# WifiAndPower.net
KiCad netlist of a schematic drawn in Altium Designer
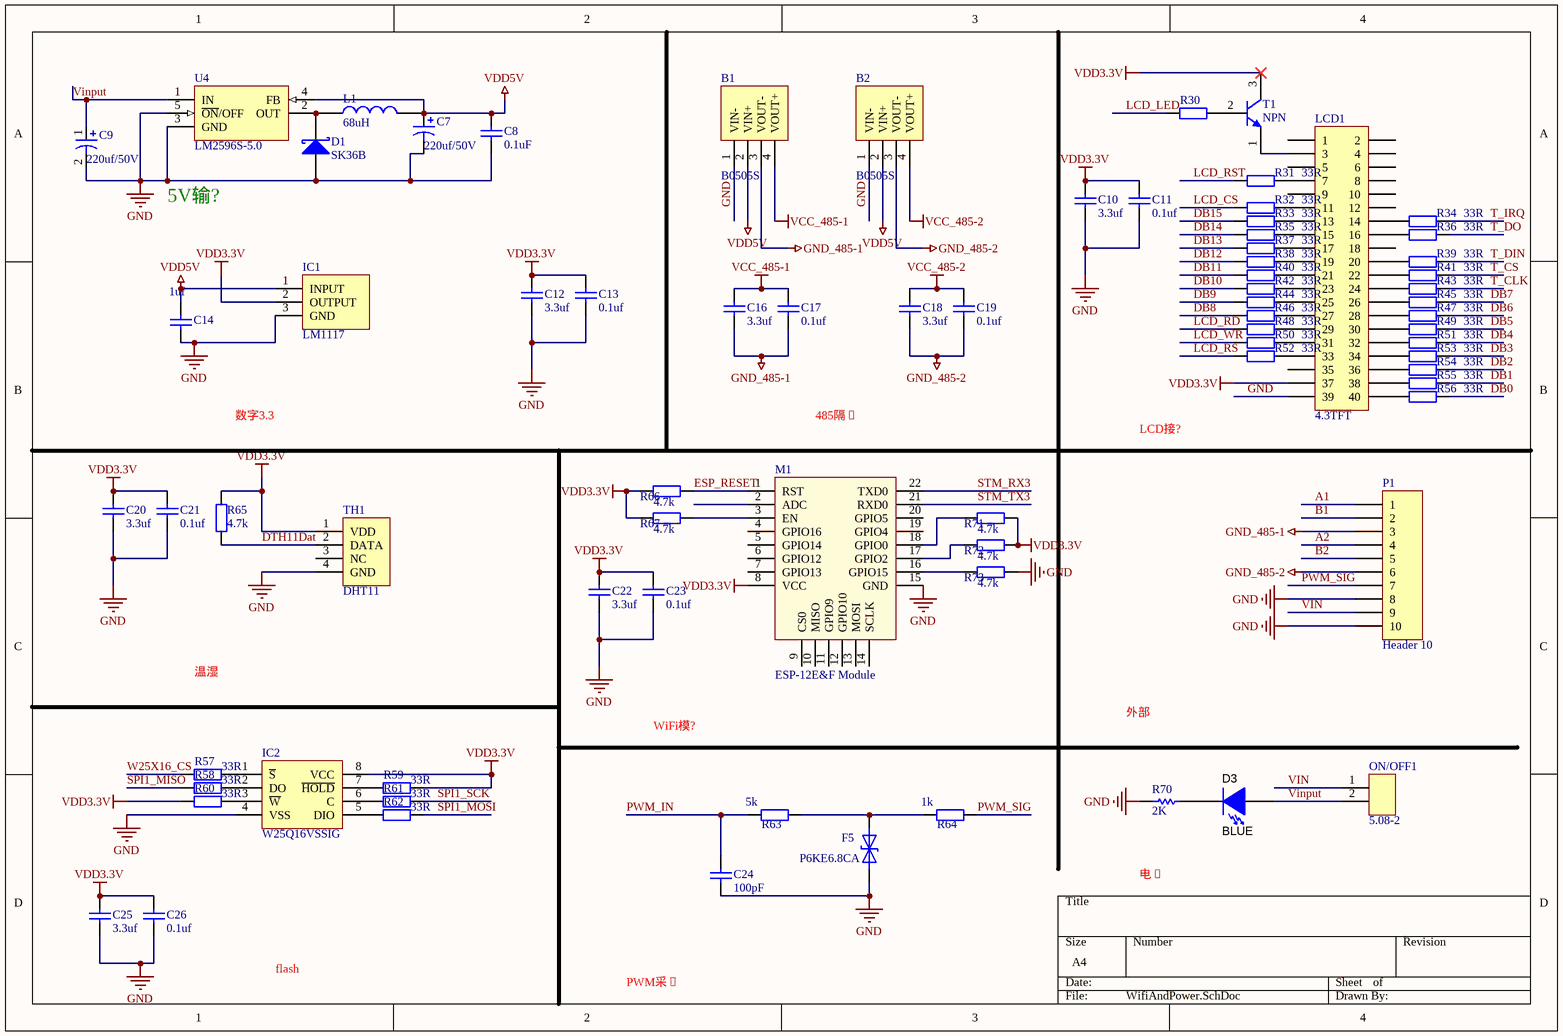
[diagram p0: WifiAndPower.SchDoc]

(export (version "E")
  (design (tool "Eeschema 10.0.6"))
  (components
    (comp (ref "B1") (value "B0505S") (footprint "B0505S") (libsource (lib "S1") (part "B0505S")))
    (comp (ref "B2") (value "B0505S") (footprint "B0505S") (libsource (lib "S1") (part "B0505S")))
    (comp (ref "C7")
      (value "220uf/50V")
      (footprint "PLAS8*10")
      (description "Polarized Capacitor (Radial)")
      (fields (field (name "Comment") "Cap Pol1") (field (name "PUBLISHER") "Altium Limited"))
      (libsource (lib "Miscellaneous Devices") (part "Cap Pol1"))
    )
    (comp (ref "C8")
      (value "0.1uF")
      (footprint "C0805")
      (description "Capacitor")
      (fields (field (name "Comment") "Cap") (field (name "PUBLISHER") "Altium Limited"))
      (libsource (lib "main board") (part "Cap_2"))
    )
    (comp (ref "C9")
      (value "220uf/50V")
      (footprint "PLAS8*10")
      (description "Polarized Capacitor (Radial)")
      (fields (field (name "Comment") "Cap Pol1") (field (name "PUBLISHER") "Altium Limited"))
      (libsource (lib "") (part "Cap Pol1_1"))
    )
    (comp (ref "C10")
      (value "3.3uf")
      (footprint "C0805")
      (description "Capacitor")
      (fields
        (field (name "MANUFACTURER") "Generic Components")
        (field (name "Comment") "Cap")
        (field (name "PUBLISHER") "Altium Hobart Technology Centre")
      )
      (libsource (lib "Miscellaneous Devices") (part "Cap"))
    )
    (comp (ref "C11")
      (value "0.1uf")
      (footprint "C0805")
      (description "Capacitor")
      (fields
        (field (name "MANUFACTURER") "Generic Components")
        (field (name "Comment") "Cap")
        (field (name "PUBLISHER") "Altium Hobart Technology Centre")
      )
      (libsource (lib "Miscellaneous Devices") (part "Cap"))
    )
    (comp (ref "C12")
      (value "3.3uf")
      (footprint "C0805")
      (description "Capacitor")
      (fields
        (field (name "MANUFACTURER") "Generic Components")
        (field (name "Comment") "Cap")
        (field (name "PUBLISHER") "Altium Hobart Technology Centre")
      )
      (libsource (lib "Miscellaneous Devices") (part "Cap"))
    )
    (comp (ref "C13")
      (value "0.1uf")
      (footprint "C0805")
      (description "Capacitor")
      (fields
        (field (name "MANUFACTURER") "Generic Components")
        (field (name "Comment") "Cap")
        (field (name "PUBLISHER") "Altium Hobart Technology Centre")
      )
      (libsource (lib "Miscellaneous Devices") (part "Cap"))
    )
    (comp (ref "C14")
      (value "1uf")
      (footprint "C0805")
      (description "Capacitor")
      (fields
        (field (name "MANUFACTURER") "Generic Components")
        (field (name "Comment") "Cap")
        (field (name "PUBLISHER") "Altium Hobart Technology Centre")
      )
      (libsource (lib "Miscellaneous Devices") (part "Cap"))
    )
    (comp (ref "C16")
      (value "3.3uf")
      (footprint "C0805")
      (description "Capacitor")
      (fields
        (field (name "MANUFACTURER") "Generic Components")
        (field (name "Comment") "Cap")
        (field (name "PUBLISHER") "Altium Hobart Technology Centre")
      )
      (libsource (lib "Miscellaneous Devices") (part "Cap"))
    )
    (comp (ref "C17")
      (value "0.1uf")
      (footprint "C0805")
      (description "Capacitor")
      (fields
        (field (name "MANUFACTURER") "Generic Components")
        (field (name "Comment") "Cap")
        (field (name "PUBLISHER") "Altium Hobart Technology Centre")
      )
      (libsource (lib "Miscellaneous Devices") (part "Cap"))
    )
    (comp (ref "C18")
      (value "3.3uf")
      (footprint "C0805")
      (description "Capacitor")
      (fields
        (field (name "MANUFACTURER") "Generic Components")
        (field (name "Comment") "Cap")
        (field (name "PUBLISHER") "Altium Hobart Technology Centre")
      )
      (libsource (lib "Miscellaneous Devices") (part "Cap"))
    )
    (comp (ref "C19")
      (value "0.1uf")
      (footprint "C0805")
      (description "Capacitor")
      (fields
        (field (name "MANUFACTURER") "Generic Components")
        (field (name "Comment") "Cap")
        (field (name "PUBLISHER") "Altium Hobart Technology Centre")
      )
      (libsource (lib "Miscellaneous Devices") (part "Cap"))
    )
    (comp (ref "C20")
      (value "3.3uf")
      (footprint "C0805")
      (description "Capacitor")
      (fields
        (field (name "MANUFACTURER") "Generic Components")
        (field (name "Comment") "Cap")
        (field (name "PUBLISHER") "Altium Hobart Technology Centre")
      )
      (libsource (lib "Miscellaneous Devices") (part "Cap"))
    )
    (comp (ref "C21")
      (value "0.1uf")
      (footprint "C0805")
      (description "Capacitor")
      (fields
        (field (name "MANUFACTURER") "Generic Components")
        (field (name "Comment") "Cap")
        (field (name "PUBLISHER") "Altium Hobart Technology Centre")
      )
      (libsource (lib "Miscellaneous Devices") (part "Cap"))
    )
    (comp (ref "C22")
      (value "3.3uf")
      (footprint "C0805")
      (description "Capacitor")
      (fields
        (field (name "MANUFACTURER") "Generic Components")
        (field (name "Comment") "Cap")
        (field (name "PUBLISHER") "Altium Hobart Technology Centre")
      )
      (libsource (lib "Miscellaneous Devices") (part "Cap"))
    )
    (comp (ref "C23")
      (value "0.1uf")
      (footprint "C0805")
      (description "Capacitor")
      (fields
        (field (name "MANUFACTURER") "Generic Components")
        (field (name "Comment") "Cap")
        (field (name "PUBLISHER") "Altium Hobart Technology Centre")
      )
      (libsource (lib "Miscellaneous Devices") (part "Cap"))
    )
    (comp (ref "C24")
      (value "100pF")
      (footprint "C0805")
      (description "Capacitor")
      (fields
        (field (name "MANUFACTURER") "Generic Components")
        (field (name "Comment") "Cap")
        (field (name "PUBLISHER") "Altium Hobart Technology Centre")
      )
      (libsource (lib "Miscellaneous Devices") (part "Cap"))
    )
    (comp (ref "C25")
      (value "3.3uf")
      (footprint "C0805")
      (description "Capacitor")
      (fields
        (field (name "MANUFACTURER") "Generic Components")
        (field (name "Comment") "Cap")
        (field (name "PUBLISHER") "Altium Hobart Technology Centre")
      )
      (libsource (lib "Miscellaneous Devices") (part "Cap"))
    )
    (comp (ref "C26")
      (value "0.1uf")
      (footprint "C0805")
      (description "Capacitor")
      (fields
        (field (name "MANUFACTURER") "Generic Components")
        (field (name "Comment") "Cap")
        (field (name "PUBLISHER") "Altium Hobart Technology Centre")
      )
      (libsource (lib "Miscellaneous Devices") (part "Cap"))
    )
    (comp (ref "D1")
      (value "SK36B")
      (footprint "SMB")
      (description "Schottky Diode")
      (fields (field (name "PUBLISHER") "Altium Limited"))
      (libsource (lib "Miscellaneous Devices") (part "D Schottky"))
    )
    (comp (ref "D3")
      (value "BLUE")
      (footprint "D0805")
      (description "LED, GREEN SMD")
      (fields
        (field (name "MANUFACTURER") "Rohm")
        (field (name "PARTNUMBER") "SML-P12YTT86")
        (field (name "PUBLISHER") "Texas Instruments")
      )
      (libsource (lib "REl") (part "SML-P12YTT86"))
    )
    (comp (ref "F5") (value "P6KE6.8CA") (description "快速瞬变二极管") (libsource (lib "*") (part "TVS")))
    (comp (ref "IC1") (value "LM1117") (footprint "LM1117") (libsource (lib "S1") (part "LM1117")))
    (comp (ref "IC2") (value "W25Q16VSSIG") (footprint "wsop8") (libsource (lib "S1") (part "A25L080")))
    (comp (ref "L1") (value "68uH") (footprint "PCBH101") (libsource (lib "µçÔ´°å") (part "INDUCTOR")))
    (comp (ref "LCD1") (value "4.3TFT") (footprint "2.4TFT") (libsource (lib "S1") (part "4.3TFT")))
    (comp (ref "M1")
      (value "ESP-12E&F Module")
      (footprint "ESP-12E&F Module")
      (libsource (lib "ESP-12E&F Module") (part "ESP-12E&F Module"))
    )
    (comp (ref "ON/OFF1") (value "5.08-2") (footprint "SensorA") (libsource (lib "S1") (part "5.08-2")))
    (comp (ref "P1")
      (value "Header 10")
      (footprint "3.5-10")
      (description "Header, 10-Pin")
      (fields (field (name "PUBLISHER") "Altium Limited"))
      (libsource (lib "Miscellaneous Connectors") (part "Header 10"))
    )
    (comp (ref "R30") (value "Res2") (footprint "0805") (libsource (lib "") (part "RES_2")))
    (comp (ref "R31")
      (value "33R")
      (footprint "0805")
      (fields (field (name "Comment") "Res2"))
      (libsource (lib "") (part "RES_2"))
    )
    (comp (ref "R32")
      (value "33R")
      (footprint "0805")
      (fields (field (name "Comment") "Res2"))
      (libsource (lib "") (part "RES_2"))
    )
    (comp (ref "R33")
      (value "33R")
      (footprint "0805")
      (fields (field (name "Comment") "Res2"))
      (libsource (lib "") (part "RES_2"))
    )
    (comp (ref "R34")
      (value "33R")
      (footprint "0805")
      (fields (field (name "Comment") "Res2"))
      (libsource (lib "") (part "RES_2"))
    )
    (comp (ref "R35")
      (value "33R")
      (footprint "0805")
      (fields (field (name "Comment") "Res2"))
      (libsource (lib "") (part "RES_2"))
    )
    (comp (ref "R36")
      (value "33R")
      (footprint "0805")
      (fields (field (name "Comment") "Res2"))
      (libsource (lib "") (part "RES_2"))
    )
    (comp (ref "R37")
      (value "33R")
      (footprint "0805")
      (fields (field (name "Comment") "Res2"))
      (libsource (lib "") (part "RES_2"))
    )
    (comp (ref "R38")
      (value "33R")
      (footprint "0805")
      (fields (field (name "Comment") "Res2"))
      (libsource (lib "") (part "RES_2"))
    )
    (comp (ref "R39")
      (value "33R")
      (footprint "0805")
      (fields (field (name "Comment") "Res2"))
      (libsource (lib "") (part "RES_2"))
    )
    (comp (ref "R40")
      (value "33R")
      (footprint "0805")
      (fields (field (name "Comment") "Res2"))
      (libsource (lib "") (part "RES_2"))
    )
    (comp (ref "R41")
      (value "33R")
      (footprint "0805")
      (fields (field (name "Comment") "Res2"))
      (libsource (lib "") (part "RES_2"))
    )
    (comp (ref "R42")
      (value "33R")
      (footprint "0805")
      (fields (field (name "Comment") "Res2"))
      (libsource (lib "") (part "RES_2"))
    )
    (comp (ref "R43")
      (value "33R")
      (footprint "0805")
      (fields (field (name "Comment") "Res2"))
      (libsource (lib "") (part "RES_2"))
    )
    (comp (ref "R44")
      (value "33R")
      (footprint "0805")
      (fields (field (name "Comment") "Res2"))
      (libsource (lib "") (part "RES_2"))
    )
    (comp (ref "R45")
      (value "33R")
      (footprint "0805")
      (fields (field (name "Comment") "Res2"))
      (libsource (lib "") (part "RES_2"))
    )
    (comp (ref "R46")
      (value "33R")
      (footprint "0805")
      (fields (field (name "Comment") "Res2"))
      (libsource (lib "") (part "RES_2"))
    )
    (comp (ref "R47")
      (value "33R")
      (footprint "0805")
      (fields (field (name "Comment") "Res2"))
      (libsource (lib "") (part "RES_2"))
    )
    (comp (ref "R48")
      (value "33R")
      (footprint "0805")
      (fields (field (name "Comment") "Res2"))
      (libsource (lib "") (part "RES_2"))
    )
    (comp (ref "R49")
      (value "33R")
      (footprint "0805")
      (fields (field (name "Comment") "Res2"))
      (libsource (lib "") (part "RES_2"))
    )
    (comp (ref "R50")
      (value "33R")
      (footprint "0805")
      (fields (field (name "Comment") "Res2"))
      (libsource (lib "") (part "RES_2"))
    )
    (comp (ref "R51")
      (value "33R")
      (footprint "0805")
      (fields (field (name "Comment") "Res2"))
      (libsource (lib "") (part "RES_2"))
    )
    (comp (ref "R52")
      (value "33R")
      (footprint "0805")
      (fields (field (name "Comment") "Res2"))
      (libsource (lib "") (part "RES_2"))
    )
    (comp (ref "R53")
      (value "33R")
      (footprint "0805")
      (fields (field (name "Comment") "Res2"))
      (libsource (lib "") (part "RES_2"))
    )
    (comp (ref "R54")
      (value "33R")
      (footprint "0805")
      (fields (field (name "Comment") "Res2"))
      (libsource (lib "") (part "RES_2"))
    )
    (comp (ref "R55")
      (value "33R")
      (footprint "0805")
      (fields (field (name "Comment") "Res2"))
      (libsource (lib "") (part "RES_2"))
    )
    (comp (ref "R56")
      (value "33R")
      (footprint "0805")
      (fields (field (name "Comment") "Res2"))
      (libsource (lib "") (part "RES_2"))
    )
    (comp (ref "R57")
      (value "33R")
      (footprint "0805")
      (fields (field (name "Comment") "Res2"))
      (libsource (lib "") (part "RES_2"))
    )
    (comp (ref "R58")
      (value "33R")
      (footprint "0805")
      (fields (field (name "Comment") "Res2"))
      (libsource (lib "") (part "RES_2"))
    )
    (comp (ref "R59")
      (value "33R")
      (footprint "0805")
      (fields (field (name "Comment") "Res2"))
      (libsource (lib "") (part "RES_2"))
    )
    (comp (ref "R60")
      (value "33R")
      (footprint "0805")
      (fields (field (name "Comment") "Res2"))
      (libsource (lib "") (part "RES_2"))
    )
    (comp (ref "R61")
      (value "33R")
      (footprint "0805")
      (fields (field (name "Comment") "Res2"))
      (libsource (lib "") (part "RES_2"))
    )
    (comp (ref "R62")
      (value "33R")
      (footprint "0805")
      (fields (field (name "Comment") "Res2"))
      (libsource (lib "") (part "RES_2"))
    )
    (comp (ref "R63")
      (value "5k")
      (footprint "0805")
      (fields (field (name "Comment") "RES"))
      (libsource (lib "S1") (part "RES"))
    )
    (comp (ref "R64")
      (value "1k")
      (footprint "0805")
      (fields (field (name "Comment") "RES"))
      (libsource (lib "S1") (part "RES"))
    )
    (comp (ref "R65")
      (value "4.7k")
      (footprint "0805")
      (fields (field (name "Comment") "Res2"))
      (libsource (lib "") (part "RES_1"))
    )
    (comp (ref "R66")
      (value "4.7k")
      (footprint "0805")
      (fields (field (name "Comment") "Res2"))
      (libsource (lib "S1") (part "RES"))
    )
    (comp (ref "R67")
      (value "4.7k")
      (footprint "0805")
      (fields (field (name "Comment") "Res2"))
      (libsource (lib "S1") (part "RES"))
    )
    (comp (ref "R70")
      (value "2K")
      (footprint "0805")
      (description "Semiconductor Resistor")
      (fields (field (name "Comment") "Res Semi") (field (name "PUBLISHER") "Altium Limited"))
      (libsource (lib "Miscellaneous Devices") (part "Res Semi"))
    )
    (comp (ref "R71")
      (value "4.7k")
      (footprint "0805")
      (fields (field (name "Comment") "Res2"))
      (libsource (lib "S1") (part "RES"))
    )
    (comp (ref "R72")
      (value "4.7k")
      (footprint "0805")
      (fields (field (name "Comment") "Res2"))
      (libsource (lib "S1") (part "RES"))
    )
    (comp (ref "R73")
      (value "4.7k")
      (footprint "0805")
      (fields (field (name "Comment") "Res2"))
      (libsource (lib "S1") (part "RES"))
    )
    (comp (ref "T1") (value "NPN") (footprint "2N3904") (libsource (lib "S1") (part "NPN")))
    (comp (ref "TH1") (value "DHT11") (footprint "DHT11") (libsource (lib "S1") (part "DHT11")))
    (comp (ref "U4")
      (value "LM2596S-5.0")
      (footprint "TS5B_M")
      (description "Simple Switcher Power Converter 150 kHz 3A Step Down Voltage Regulator")
      (fields (field (name "PUBLISHER") "Altium Limited"))
      (libsource (lib "NSC Power Mgt Switching Regulator") (part "LM2596S-5.0"))
    )
  )
  (nets
    (net (code "1") (name "/A1") (class "Default")
      (node (ref "P1") (pin "1") (pinfunction "1_1") (pintype "passive"))
    )
    (net (code "2") (name "/A2") (class "Default")
      (node (ref "P1") (pin "4") (pinfunction "4_4") (pintype "passive"))
    )
    (net (code "3") (name "/B1") (class "Default")
      (node (ref "P1") (pin "2") (pinfunction "2_2") (pintype "passive"))
    )
    (net (code "4") (name "/B2") (class "Default")
      (node (ref "P1") (pin "5") (pinfunction "5_5") (pintype "passive"))
    )
    (net (code "5") (name "/DB0") (class "Default")
      (node (ref "R56") (pin "2") (pinfunction "2_2") (pintype "passive"))
    )
    (net (code "6") (name "/DB1") (class "Default")
      (node (ref "R55") (pin "2") (pinfunction "2_2") (pintype "passive"))
    )
    (net (code "7") (name "/DB2") (class "Default")
      (node (ref "R54") (pin "2") (pinfunction "2_2") (pintype "passive"))
    )
    (net (code "8") (name "/DB3") (class "Default")
      (node (ref "R53") (pin "2") (pinfunction "2_2") (pintype "passive"))
    )
    (net (code "9") (name "/DB4") (class "Default")
      (node (ref "R51") (pin "2") (pinfunction "2_2") (pintype "passive"))
    )
    (net (code "10") (name "/DB5") (class "Default")
      (node (ref "R49") (pin "2") (pinfunction "2_2") (pintype "passive"))
    )
    (net (code "11") (name "/DB6") (class "Default")
      (node (ref "R47") (pin "2") (pinfunction "2_2") (pintype "passive"))
    )
    (net (code "12") (name "/DB7") (class "Default")
      (node (ref "R45") (pin "2") (pinfunction "2_2") (pintype "passive"))
    )
    (net (code "13") (name "/DB8") (class "Default")
      (node (ref "R46") (pin "1") (pinfunction "1_1") (pintype "passive"))
    )
    (net (code "14") (name "/DB9") (class "Default")
      (node (ref "R44") (pin "1") (pinfunction "1_1") (pintype "passive"))
    )
    (net (code "15") (name "/DB10") (class "Default")
      (node (ref "R42") (pin "1") (pinfunction "1_1") (pintype "passive"))
    )
    (net (code "16") (name "/DB11") (class "Default")
      (node (ref "R40") (pin "1") (pinfunction "1_1") (pintype "passive"))
    )
    (net (code "17") (name "/DB12") (class "Default")
      (node (ref "R38") (pin "1") (pinfunction "1_1") (pintype "passive"))
    )
    (net (code "18") (name "/DB13") (class "Default")
      (node (ref "R37") (pin "1") (pinfunction "1_1") (pintype "passive"))
    )
    (net (code "19") (name "/DB14") (class "Default")
      (node (ref "R35") (pin "1") (pinfunction "1_1") (pintype "passive"))
    )
    (net (code "20") (name "/DB15") (class "Default")
      (node (ref "R33") (pin "1") (pinfunction "1_1") (pintype "passive"))
    )
    (net (code "21") (name "/DTH11Dat") (class "Default")
      (node (ref "R65") (pin "1") (pinfunction "1_1") (pintype "passive"))
      (node (ref "TH1") (pin "2") (pinfunction "DATA_2") (pintype "passive"))
    )
    (net (code "22") (name "/ESP_RESET") (class "Default")
      (node (ref "M1") (pin "1") (pinfunction "RST_1") (pintype "passive"))
      (node (ref "R66") (pin "1") (pinfunction "1_1") (pintype "passive"))
    )
    (net (code "23") (name "/LCD_CS") (class "Default")
      (node (ref "R32") (pin "1") (pinfunction "1_1") (pintype "passive"))
    )
    (net (code "24") (name "/LCD_LED") (class "Default")
      (node (ref "R30") (pin "1") (pinfunction "1_1") (pintype "passive"))
    )
    (net (code "25") (name "/LCD_RD") (class "Default")
      (node (ref "R48") (pin "1") (pinfunction "1_1") (pintype "passive"))
    )
    (net (code "26") (name "/LCD_RS") (class "Default")
      (node (ref "R52") (pin "1") (pinfunction "1_1") (pintype "passive"))
    )
    (net (code "27") (name "/LCD_RST") (class "Default")
      (node (ref "R31") (pin "1") (pinfunction "1_1") (pintype "passive"))
    )
    (net (code "28") (name "/LCD_WR") (class "Default")
      (node (ref "R50") (pin "1") (pinfunction "1_1") (pintype "passive"))
    )
    (net (code "29") (name "/PWM_IN") (class "Default")
      (node (ref "C24") (pin "1") (pinfunction "1_1") (pintype "passive"))
      (node (ref "R63") (pin "2") (pinfunction "2_2") (pintype "passive"))
    )
    (net (code "30") (name "/PWM_SIG") (class "Default")
      (node (ref "P1") (pin "7") (pinfunction "7_7") (pintype "passive"))
      (node (ref "R64") (pin "1") (pinfunction "1_1") (pintype "passive"))
    )
    (net (code "31") (name "/SPI1_MISO") (class "Default")
      (node (ref "R58") (pin "1") (pinfunction "1_1") (pintype "passive"))
    )
    (net (code "32") (name "/SPI1_MOSI") (class "Default")
      (node (ref "R62") (pin "2") (pinfunction "2_2") (pintype "passive"))
    )
    (net (code "33") (name "/SPI1_SCK") (class "Default")
      (node (ref "R61") (pin "2") (pinfunction "2_2") (pintype "passive"))
    )
    (net (code "34") (name "/STM_RX3") (class "Default")
      (node (ref "M1") (pin "22") (pinfunction "TXD0_22") (pintype "passive"))
    )
    (net (code "35") (name "/STM_TX3") (class "Default")
      (node (ref "M1") (pin "21") (pinfunction "RXD0_21") (pintype "passive"))
    )
    (net (code "36") (name "/T_CLK") (class "Default")
      (node (ref "R43") (pin "2") (pinfunction "2_2") (pintype "passive"))
    )
    (net (code "37") (name "/T_CS") (class "Default")
      (node (ref "R41") (pin "2") (pinfunction "2_2") (pintype "passive"))
    )
    (net (code "38") (name "/T_DIN") (class "Default")
      (node (ref "R39") (pin "2") (pinfunction "2_2") (pintype "passive"))
    )
    (net (code "39") (name "/T_DO") (class "Default")
      (node (ref "R36") (pin "2") (pinfunction "2_2") (pintype "passive"))
    )
    (net (code "40") (name "/T_IRQ") (class "Default")
      (node (ref "R34") (pin "2") (pinfunction "2_2") (pintype "passive"))
    )
    (net (code "41") (name "/VIN") (class "Default")
      (node (ref "ON/OFF1") (pin "1") (pintype "passive"))
      (node (ref "P1") (pin "9") (pinfunction "9_9") (pintype "passive"))
    )
    (net (code "42") (name "/Vinput") (class "Default")
      (node (ref "C9") (pin "1") (pinfunction "1_1") (pintype "passive"))
      (node (ref "D3") (pin "1") (pinfunction "A_1") (pintype "passive"))
      (node (ref "ON/OFF1") (pin "2") (pintype "passive"))
      (node (ref "U4") (pin "1") (pinfunction "IN_1") (pintype "power_in"))
    )
    (net (code "43") (name "/W25X16_CS") (class "Default")
      (node (ref "R57") (pin "1") (pinfunction "1_1") (pintype "passive"))
    )
    (net (code "44") (name "GND") (class "Default")
      (node (ref "B1") (pin "1") (pinfunction "VIN-_1") (pintype "passive"))
      (node (ref "B2") (pin "1") (pinfunction "VIN-_1") (pintype "passive"))
      (node (ref "C10") (pin "2") (pinfunction "2_2") (pintype "passive"))
      (node (ref "C11") (pin "2") (pinfunction "2_2") (pintype "passive"))
      (node (ref "C12") (pin "2") (pinfunction "2_2") (pintype "passive"))
      (node (ref "C13") (pin "2") (pinfunction "2_2") (pintype "passive"))
      (node (ref "C14") (pin "2") (pinfunction "2_2") (pintype "passive"))
      (node (ref "C20") (pin "2") (pinfunction "2_2") (pintype "passive"))
      (node (ref "C21") (pin "2") (pinfunction "2_2") (pintype "passive"))
      (node (ref "C22") (pin "2") (pinfunction "2_2") (pintype "passive"))
      (node (ref "C23") (pin "2") (pinfunction "2_2") (pintype "passive"))
      (node (ref "C24") (pin "2") (pinfunction "2_2") (pintype "passive"))
      (node (ref "C25") (pin "2") (pinfunction "2_2") (pintype "passive"))
      (node (ref "C26") (pin "2") (pinfunction "2_2") (pintype "passive"))
      (node (ref "C7") (pin "2") (pinfunction "2_2") (pintype "passive"))
      (node (ref "C8") (pin "1") (pinfunction "1_1") (pintype "passive"))
      (node (ref "C9") (pin "2") (pinfunction "2_2") (pintype "passive"))
      (node (ref "D1") (pin "1") (pinfunction "A_1") (pintype "passive"))
      (node (ref "F5") (pin "2") (pintype "passive"))
      (node (ref "IC1") (pin "3") (pinfunction "GND_3") (pintype "passive"))
      (node (ref "IC2") (pin "4") (pinfunction "VSS_4") (pintype "passive"))
      (node (ref "LCD1") (pin "39") (pinfunction "39_39") (pintype "passive"))
      (node (ref "M1") (pin "15") (pinfunction "GND_15") (pintype "passive"))
      (node (ref "P1") (pin "10") (pinfunction "10_10") (pintype "passive"))
      (node (ref "P1") (pin "8") (pinfunction "8_8") (pintype "passive"))
      (node (ref "R70") (pin "2") (pinfunction "2_2") (pintype "passive"))
      (node (ref "R73") (pin "1") (pinfunction "1_1") (pintype "passive"))
      (node (ref "TH1") (pin "4") (pinfunction "GND_4") (pintype "passive"))
      (node (ref "U4") (pin "3") (pinfunction "GND_3") (pintype "power_in"))
      (node (ref "U4") (pin "5") (pinfunction "~{ON}/OFF_5") (pintype "input"))
    )
    (net (code "45") (name "GND_485-1") (class "Default")
      (node (ref "B1") (pin "3") (pinfunction "VOUT-_3") (pintype "passive"))
      (node (ref "C16") (pin "2") (pinfunction "2_2") (pintype "passive"))
      (node (ref "C17") (pin "2") (pinfunction "2_2") (pintype "passive"))
      (node (ref "P1") (pin "3") (pinfunction "3_3") (pintype "passive"))
    )
    (net (code "46") (name "GND_485-2") (class "Default")
      (node (ref "B2") (pin "3") (pinfunction "VOUT-_3") (pintype "passive"))
      (node (ref "C18") (pin "2") (pinfunction "2_2") (pintype "passive"))
      (node (ref "C19") (pin "2") (pinfunction "2_2") (pintype "passive"))
      (node (ref "P1") (pin "6") (pinfunction "6_6") (pintype "passive"))
    )
    (net (code "47") (name "Net-(D1-K)") (class "Default")
      (node (ref "D1") (pin "2") (pinfunction "K_2") (pintype "passive"))
      (node (ref "L1") (pin "1") (pinfunction "1_1") (pintype "passive"))
      (node (ref "U4") (pin "2") (pinfunction "OUT_2") (pintype "power_in"))
    )
    (net (code "48") (name "Net-(D3-K)") (class "Default")
      (node (ref "D3") (pin "2") (pinfunction "K_2") (pintype "passive"))
      (node (ref "R70") (pin "1") (pinfunction "1_1") (pintype "passive"))
    )
    (net (code "49") (name "Net-(F5-Pad1)") (class "Default")
      (node (ref "F5") (pin "1") (pintype "passive"))
      (node (ref "R63") (pin "1") (pinfunction "1_1") (pintype "passive"))
      (node (ref "R64") (pin "2") (pinfunction "2_2") (pintype "passive"))
    )
    (net (code "50") (name "Net-(IC2-C)") (class "Default")
      (node (ref "IC2") (pin "6") (pinfunction "C_6") (pintype "passive"))
      (node (ref "R61") (pin "1") (pinfunction "1_1") (pintype "passive"))
    )
    (net (code "51") (name "Net-(IC2-DIO)") (class "Default")
      (node (ref "IC2") (pin "5") (pinfunction "DIO_5") (pintype "passive"))
      (node (ref "R62") (pin "1") (pinfunction "1_1") (pintype "passive"))
    )
    (net (code "52") (name "Net-(IC2-DO)") (class "Default")
      (node (ref "IC2") (pin "2") (pinfunction "DO_2") (pintype "passive"))
      (node (ref "R58") (pin "2") (pinfunction "2_2") (pintype "passive"))
    )
    (net (code "53") (name "Net-(IC2-~{HOLD})") (class "Default")
      (node (ref "IC2") (pin "7") (pinfunction "~{HOLD}_7") (pintype "passive"))
      (node (ref "R59") (pin "1") (pinfunction "1_1") (pintype "passive"))
    )
    (net (code "54") (name "Net-(IC2-~{S})") (class "Default")
      (node (ref "IC2") (pin "1") (pinfunction "~{S}_1") (pintype "passive"))
      (node (ref "R57") (pin "2") (pinfunction "2_2") (pintype "passive"))
    )
    (net (code "55") (name "Net-(IC2-~{W})") (class "Default")
      (node (ref "IC2") (pin "3") (pinfunction "~{W}_3") (pintype "passive"))
      (node (ref "R60") (pin "2") (pinfunction "2_2") (pintype "passive"))
    )
    (net (code "56") (name "Net-(LCD1-Pad7)") (class "Default")
      (node (ref "LCD1") (pin "7") (pinfunction "7_7") (pintype "passive"))
      (node (ref "R31") (pin "2") (pinfunction "2_2") (pintype "passive"))
    )
    (net (code "57") (name "Net-(LCD1-Pad11)") (class "Default")
      (node (ref "LCD1") (pin "11") (pinfunction "11_11") (pintype "passive"))
      (node (ref "R32") (pin "2") (pinfunction "2_2") (pintype "passive"))
    )
    (net (code "58") (name "Net-(LCD1-Pad13)") (class "Default")
      (node (ref "LCD1") (pin "13") (pinfunction "13_13") (pintype "passive"))
      (node (ref "R33") (pin "2") (pinfunction "2_2") (pintype "passive"))
    )
    (net (code "59") (name "Net-(LCD1-Pad14)") (class "Default")
      (node (ref "LCD1") (pin "14") (pinfunction "14_14") (pintype "passive"))
      (node (ref "R34") (pin "1") (pinfunction "1_1") (pintype "passive"))
    )
    (net (code "60") (name "Net-(LCD1-Pad15)") (class "Default")
      (node (ref "LCD1") (pin "15") (pinfunction "15_15") (pintype "passive"))
      (node (ref "R35") (pin "2") (pinfunction "2_2") (pintype "passive"))
    )
    (net (code "61") (name "Net-(LCD1-Pad16)") (class "Default")
      (node (ref "LCD1") (pin "16") (pinfunction "16_16") (pintype "passive"))
      (node (ref "R36") (pin "1") (pinfunction "1_1") (pintype "passive"))
    )
    (net (code "62") (name "Net-(LCD1-Pad17)") (class "Default")
      (node (ref "LCD1") (pin "17") (pinfunction "17_17") (pintype "passive"))
      (node (ref "R37") (pin "2") (pinfunction "2_2") (pintype "passive"))
    )
    (net (code "63") (name "Net-(LCD1-Pad19)") (class "Default")
      (node (ref "LCD1") (pin "19") (pinfunction "19_19") (pintype "passive"))
      (node (ref "R38") (pin "2") (pinfunction "2_2") (pintype "passive"))
    )
    (net (code "64") (name "Net-(LCD1-Pad20)") (class "Default")
      (node (ref "LCD1") (pin "20") (pinfunction "20_20") (pintype "passive"))
      (node (ref "R39") (pin "1") (pinfunction "1_1") (pintype "passive"))
    )
    (net (code "65") (name "Net-(LCD1-Pad21)") (class "Default")
      (node (ref "LCD1") (pin "21") (pinfunction "21_21") (pintype "passive"))
      (node (ref "R40") (pin "2") (pinfunction "2_2") (pintype "passive"))
    )
    (net (code "66") (name "Net-(LCD1-Pad22)") (class "Default")
      (node (ref "LCD1") (pin "22") (pinfunction "22_22") (pintype "passive"))
      (node (ref "R41") (pin "1") (pinfunction "1_1") (pintype "passive"))
    )
    (net (code "67") (name "Net-(LCD1-Pad23)") (class "Default")
      (node (ref "LCD1") (pin "23") (pinfunction "23_23") (pintype "passive"))
      (node (ref "R42") (pin "2") (pinfunction "2_2") (pintype "passive"))
    )
    (net (code "68") (name "Net-(LCD1-Pad24)") (class "Default")
      (node (ref "LCD1") (pin "24") (pinfunction "24_24") (pintype "passive"))
      (node (ref "R43") (pin "1") (pinfunction "1_1") (pintype "passive"))
    )
    (net (code "69") (name "Net-(LCD1-Pad25)") (class "Default")
      (node (ref "LCD1") (pin "25") (pinfunction "25_25") (pintype "passive"))
      (node (ref "R44") (pin "2") (pinfunction "2_2") (pintype "passive"))
    )
    (net (code "70") (name "Net-(LCD1-Pad26)") (class "Default")
      (node (ref "LCD1") (pin "26") (pinfunction "26_26") (pintype "passive"))
      (node (ref "R45") (pin "1") (pinfunction "1_1") (pintype "passive"))
    )
    (net (code "71") (name "Net-(LCD1-Pad27)") (class "Default")
      (node (ref "LCD1") (pin "27") (pinfunction "27_27") (pintype "passive"))
      (node (ref "R46") (pin "2") (pinfunction "2_2") (pintype "passive"))
    )
    (net (code "72") (name "Net-(LCD1-Pad28)") (class "Default")
      (node (ref "LCD1") (pin "28") (pinfunction "28_28") (pintype "passive"))
      (node (ref "R47") (pin "1") (pinfunction "1_1") (pintype "passive"))
    )
    (net (code "73") (name "Net-(LCD1-Pad29)") (class "Default")
      (node (ref "LCD1") (pin "29") (pinfunction "29_29") (pintype "passive"))
      (node (ref "R48") (pin "2") (pinfunction "2_2") (pintype "passive"))
    )
    (net (code "74") (name "Net-(LCD1-Pad30)") (class "Default")
      (node (ref "LCD1") (pin "30") (pinfunction "30_30") (pintype "passive"))
      (node (ref "R49") (pin "1") (pinfunction "1_1") (pintype "passive"))
    )
    (net (code "75") (name "Net-(LCD1-Pad31)") (class "Default")
      (node (ref "LCD1") (pin "31") (pinfunction "31_31") (pintype "passive"))
      (node (ref "R50") (pin "2") (pinfunction "2_2") (pintype "passive"))
    )
    (net (code "76") (name "Net-(LCD1-Pad32)") (class "Default")
      (node (ref "LCD1") (pin "32") (pinfunction "32_32") (pintype "passive"))
      (node (ref "R51") (pin "1") (pinfunction "1_1") (pintype "passive"))
    )
    (net (code "77") (name "Net-(LCD1-Pad33)") (class "Default")
      (node (ref "LCD1") (pin "33") (pinfunction "33_33") (pintype "passive"))
      (node (ref "R52") (pin "2") (pinfunction "2_2") (pintype "passive"))
    )
    (net (code "78") (name "Net-(LCD1-Pad34)") (class "Default")
      (node (ref "LCD1") (pin "34") (pinfunction "34_34") (pintype "passive"))
      (node (ref "R53") (pin "1") (pinfunction "1_1") (pintype "passive"))
    )
    (net (code "79") (name "Net-(LCD1-Pad36)") (class "Default")
      (node (ref "LCD1") (pin "36") (pinfunction "36_36") (pintype "passive"))
      (node (ref "R54") (pin "1") (pinfunction "1_1") (pintype "passive"))
    )
    (net (code "80") (name "Net-(LCD1-Pad38)") (class "Default")
      (node (ref "LCD1") (pin "38") (pinfunction "38_38") (pintype "passive"))
      (node (ref "R55") (pin "1") (pinfunction "1_1") (pintype "passive"))
    )
    (net (code "81") (name "Net-(LCD1-Pad40)") (class "Default")
      (node (ref "LCD1") (pin "40") (pinfunction "40_40") (pintype "passive"))
      (node (ref "R56") (pin "1") (pinfunction "1_1") (pintype "passive"))
    )
    (net (code "82") (name "Net-(M1-EN)") (class "Default")
      (node (ref "M1") (pin "3") (pinfunction "EN_3") (pintype "passive"))
      (node (ref "R67") (pin "1") (pinfunction "1_1") (pintype "passive"))
    )
    (net (code "83") (name "Net-(M1-GPIO0)") (class "Default")
      (node (ref "M1") (pin "18") (pinfunction "GPIO0_18") (pintype "passive"))
      (node (ref "R71") (pin "2") (pinfunction "2_2") (pintype "passive"))
    )
    (net (code "84") (name "Net-(M1-GPIO2)") (class "Default")
      (node (ref "M1") (pin "17") (pinfunction "GPIO2_17") (pintype "passive"))
      (node (ref "R72") (pin "2") (pinfunction "2_2") (pintype "passive"))
    )
    (net (code "85") (name "Net-(M1-GPIO15)") (class "Default")
      (node (ref "M1") (pin "16") (pinfunction "GPIO15_16") (pintype "passive"))
      (node (ref "R73") (pin "2") (pinfunction "2_2") (pintype "passive"))
    )
    (net (code "86") (name "Net-(T1-B)") (class "Default")
      (node (ref "R30") (pin "2") (pinfunction "2_2") (pintype "passive"))
      (node (ref "T1") (pin "2") (pinfunction "B_2") (pintype "passive"))
    )
    (net (code "87") (name "Net-(T1-E)") (class "Default")
      (node (ref "LCD1") (pin "3") (pinfunction "3_3") (pintype "passive"))
      (node (ref "T1") (pin "1") (pinfunction "E_1") (pintype "passive"))
    )
    (net (code "88") (name "VCC_485-1") (class "Default")
      (node (ref "B1") (pin "4") (pinfunction "VOUT+_4") (pintype "passive"))
      (node (ref "C16") (pin "1") (pinfunction "1_1") (pintype "passive"))
      (node (ref "C17") (pin "1") (pinfunction "1_1") (pintype "passive"))
    )
    (net (code "89") (name "VCC_485-2") (class "Default")
      (node (ref "B2") (pin "4") (pinfunction "VOUT+_4") (pintype "passive"))
      (node (ref "C18") (pin "1") (pinfunction "1_1") (pintype "passive"))
      (node (ref "C19") (pin "1") (pinfunction "1_1") (pintype "passive"))
    )
    (net (code "90") (name "VDD3.3V") (class "Default")
      (node (ref "C10") (pin "1") (pinfunction "1_1") (pintype "passive"))
      (node (ref "C11") (pin "1") (pinfunction "1_1") (pintype "passive"))
      (node (ref "C12") (pin "1") (pinfunction "1_1") (pintype "passive"))
      (node (ref "C13") (pin "1") (pinfunction "1_1") (pintype "passive"))
      (node (ref "C20") (pin "1") (pinfunction "1_1") (pintype "passive"))
      (node (ref "C21") (pin "1") (pinfunction "1_1") (pintype "passive"))
      (node (ref "C22") (pin "1") (pinfunction "1_1") (pintype "passive"))
      (node (ref "C23") (pin "1") (pinfunction "1_1") (pintype "passive"))
      (node (ref "C25") (pin "1") (pinfunction "1_1") (pintype "passive"))
      (node (ref "C26") (pin "1") (pinfunction "1_1") (pintype "passive"))
      (node (ref "IC1") (pin "2") (pinfunction "OUTPUT_2") (pintype "passive"))
      (node (ref "IC2") (pin "8") (pinfunction "VCC_8") (pintype "passive"))
      (node (ref "LCD1") (pin "37") (pinfunction "37_37") (pintype "passive"))
      (node (ref "M1") (pin "8") (pinfunction "VCC_8") (pintype "passive"))
      (node (ref "R59") (pin "2") (pinfunction "2_2") (pintype "passive"))
      (node (ref "R60") (pin "1") (pinfunction "1_1") (pintype "passive"))
      (node (ref "R65") (pin "2") (pinfunction "2_2") (pintype "passive"))
      (node (ref "R66") (pin "2") (pinfunction "2_2") (pintype "passive"))
      (node (ref "R67") (pin "2") (pinfunction "2_2") (pintype "passive"))
      (node (ref "R71") (pin "1") (pinfunction "1_1") (pintype "passive"))
      (node (ref "R72") (pin "1") (pinfunction "1_1") (pintype "passive"))
      (node (ref "T1") (pin "3") (pinfunction "C_3") (pintype "passive"))
      (node (ref "TH1") (pin "1") (pinfunction "VDD_1") (pintype "passive"))
    )
    (net (code "91") (name "VDD5V") (class "Default")
      (node (ref "B1") (pin "2") (pinfunction "VIN+_2") (pintype "passive"))
      (node (ref "B2") (pin "2") (pinfunction "VIN+_2") (pintype "passive"))
      (node (ref "C14") (pin "1") (pinfunction "1_1") (pintype "passive"))
      (node (ref "C7") (pin "1") (pinfunction "1_1") (pintype "passive"))
      (node (ref "C8") (pin "2") (pinfunction "2_2") (pintype "passive"))
      (node (ref "IC1") (pin "1") (pinfunction "INPUT_1") (pintype "passive"))
      (node (ref "L1") (pin "2") (pinfunction "2_2") (pintype "passive"))
      (node (ref "U4") (pin "4") (pinfunction "FB_4") (pintype "input"))
    )
    (net (code "92") (name "unconnected-(LCD1-Pad1)") (class "Default")
      (node (ref "LCD1") (pin "1") (pinfunction "1_1") (pintype "passive"))
    )
    (net (code "93") (name "unconnected-(LCD1-Pad2)") (class "Default")
      (node (ref "LCD1") (pin "2") (pinfunction "2_2") (pintype "passive"))
    )
    (net (code "94") (name "unconnected-(LCD1-Pad4)") (class "Default")
      (node (ref "LCD1") (pin "4") (pinfunction "4_4") (pintype "passive"))
    )
    (net (code "95") (name "unconnected-(LCD1-Pad5)") (class "Default")
      (node (ref "LCD1") (pin "5") (pinfunction "5_5") (pintype "passive"))
    )
    (net (code "96") (name "unconnected-(LCD1-Pad6)") (class "Default")
      (node (ref "LCD1") (pin "6") (pinfunction "6_6") (pintype "passive"))
    )
    (net (code "97") (name "unconnected-(LCD1-Pad8)") (class "Default")
      (node (ref "LCD1") (pin "8") (pinfunction "8_8") (pintype "passive"))
    )
    (net (code "98") (name "unconnected-(LCD1-Pad9)") (class "Default")
      (node (ref "LCD1") (pin "9") (pinfunction "9_9") (pintype "passive"))
    )
    (net (code "99") (name "unconnected-(LCD1-Pad10)") (class "Default")
      (node (ref "LCD1") (pin "10") (pinfunction "10_10") (pintype "passive"))
    )
    (net (code "100") (name "unconnected-(LCD1-Pad12)") (class "Default")
      (node (ref "LCD1") (pin "12") (pinfunction "12_12") (pintype "passive"))
    )
    (net (code "101") (name "unconnected-(LCD1-Pad18)") (class "Default")
      (node (ref "LCD1") (pin "18") (pinfunction "18_18") (pintype "passive"))
    )
    (net (code "102") (name "unconnected-(LCD1-Pad35)") (class "Default")
      (node (ref "LCD1") (pin "35") (pinfunction "35_35") (pintype "passive"))
    )
    (net (code "103") (name "unconnected-(M1-ADC-Pad2)") (class "Default")
      (node (ref "M1") (pin "2") (pinfunction "ADC_2") (pintype "passive"))
    )
    (net (code "104") (name "unconnected-(M1-CS0-Pad9)") (class "Default")
      (node (ref "M1") (pin "9") (pinfunction "CS0_9") (pintype "passive"))
    )
    (net (code "105") (name "unconnected-(M1-GPIO4-Pad19)") (class "Default")
      (node (ref "M1") (pin "19") (pinfunction "GPIO4_19") (pintype "passive"))
    )
    (net (code "106") (name "unconnected-(M1-GPIO5-Pad20)") (class "Default")
      (node (ref "M1") (pin "20") (pinfunction "GPIO5_20") (pintype "passive"))
    )
    (net (code "107") (name "unconnected-(M1-GPIO9-Pad11)") (class "Default")
      (node (ref "M1") (pin "11") (pinfunction "GPIO9_11") (pintype "passive"))
    )
    (net (code "108") (name "unconnected-(M1-GPIO10-Pad12)") (class "Default")
      (node (ref "M1") (pin "12") (pinfunction "GPIO10_12") (pintype "passive"))
    )
    (net (code "109") (name "unconnected-(M1-GPIO12-Pad6)") (class "Default")
      (node (ref "M1") (pin "6") (pinfunction "GPIO12_6") (pintype "passive"))
    )
    (net (code "110") (name "unconnected-(M1-GPIO13-Pad7)") (class "Default")
      (node (ref "M1") (pin "7") (pinfunction "GPIO13_7") (pintype "passive"))
    )
    (net (code "111") (name "unconnected-(M1-GPIO14-Pad5)") (class "Default")
      (node (ref "M1") (pin "5") (pinfunction "GPIO14_5") (pintype "passive"))
    )
    (net (code "112") (name "unconnected-(M1-GPIO16-Pad4)") (class "Default")
      (node (ref "M1") (pin "4") (pinfunction "GPIO16_4") (pintype "passive"))
    )
    (net (code "113") (name "unconnected-(M1-MISO-Pad10)") (class "Default")
      (node (ref "M1") (pin "10") (pinfunction "MISO_10") (pintype "passive"))
    )
    (net (code "114") (name "unconnected-(M1-MOSI-Pad13)") (class "Default")
      (node (ref "M1") (pin "13") (pinfunction "MOSI_13") (pintype "passive"))
    )
    (net (code "115") (name "unconnected-(M1-SCLK-Pad14)") (class "Default")
      (node (ref "M1") (pin "14") (pinfunction "SCLK_14") (pintype "passive"))
    )
    (net (code "116") (name "unconnected-(TH1-NC-Pad3)") (class "Default")
      (node (ref "TH1") (pin "3") (pinfunction "NC_3") (pintype "passive"))
    )
  )
)
